# bbSMDuino_v1.net
KiCad netlist of a schematic drawn in EAGLE
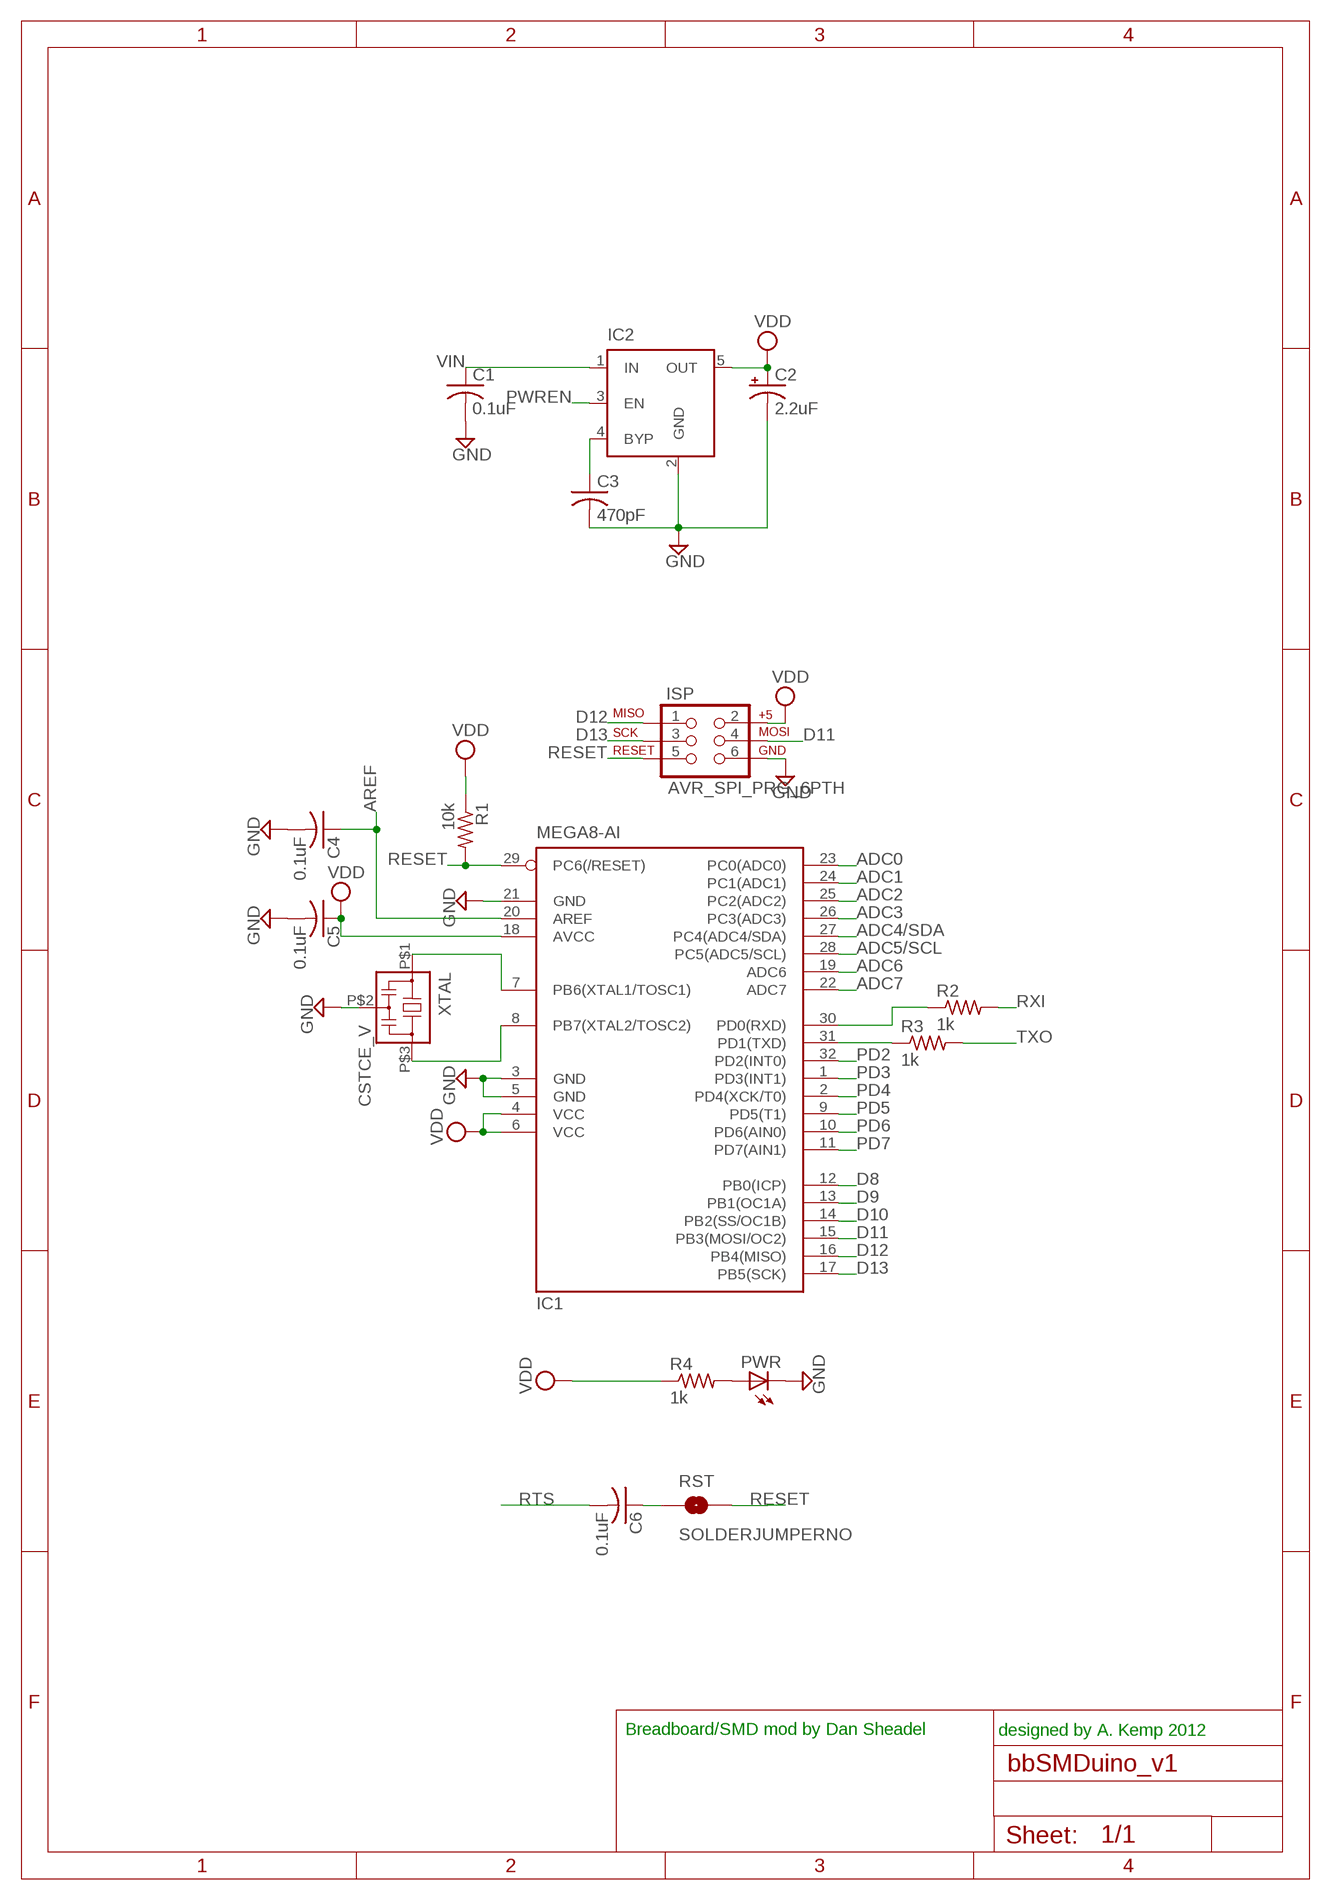
[diagram p0: schematic, sheet 1]

(export (version "E")
  (design (tool "Eeschema 10.0.6"))
  (components
    (comp (ref "C1")
      (value "0.1uF")
      (footprint "eagle-import:C0603")
      (libsource (lib "eagle-import") (part "C-USC0603"))
    )
    (comp (ref "C2")
      (value "2.2uF")
      (footprint "eagle-import:CT3216")
      (libsource (lib "eagle-import") (part "CPOL-USCT3216"))
    )
    (comp (ref "C3")
      (value "470pF")
      (footprint "eagle-import:C0603")
      (libsource (lib "eagle-import") (part "C-USC0603"))
    )
    (comp (ref "C4")
      (value "0.1uF")
      (footprint "eagle-import:C0603")
      (libsource (lib "eagle-import") (part "C-USC0603"))
    )
    (comp (ref "C5")
      (value "0.1uF")
      (footprint "eagle-import:C0603")
      (libsource (lib "eagle-import") (part "C-USC0603"))
    )
    (comp (ref "C6")
      (value "0.1uF")
      (footprint "eagle-import:C0603")
      (libsource (lib "eagle-import") (part "C-USC0603"))
    )
    (comp (ref "IC1")
      (value "MEGA8-AI")
      (footprint "eagle-import:TQFP32-08")
      (libsource (lib "eagle-import") (part "MEGA8-AI"))
    )
    (comp (ref "IC2")
      (value "MIC5219XX")
      (footprint "eagle-import:SOT23-5")
      (libsource (lib "eagle-import") (part "MIC5219XX"))
    )
    (comp (ref "ISP")
      (value "AVR_SPI_PRG_6PTH")
      (footprint "eagle-import:2X3")
      (libsource (lib "eagle-import") (part "AVR_SPI_PRG_6PTH"))
    )
    (comp (ref "PWR")
      (value "LEDCHIP-LED0603")
      (footprint "eagle-import:CHIP-LED0603")
      (libsource (lib "eagle-import") (part "LEDCHIP-LED0603"))
    )
    (comp (ref "R1")
      (value "10k")
      (footprint "eagle-import:R0603")
      (libsource (lib "eagle-import") (part "R-US_R0603"))
    )
    (comp (ref "R2")
      (value "1k")
      (footprint "eagle-import:R0603")
      (libsource (lib "eagle-import") (part "R-US_R0603"))
    )
    (comp (ref "R3")
      (value "1k")
      (footprint "eagle-import:R0603")
      (libsource (lib "eagle-import") (part "R-US_R0603"))
    )
    (comp (ref "R4")
      (value "1k")
      (footprint "eagle-import:R0603")
      (libsource (lib "eagle-import") (part "R-US_R0603"))
    )
    (comp (ref "RST")
      (value "SOLDERJUMPERNO")
      (footprint "eagle-import:SJ_2S-NO")
      (libsource (lib "eagle-import") (part "SOLDERJUMPERNO"))
    )
    (comp (ref "XTAL")
      (value "CSTCE_V")
      (footprint "eagle-import:CSTCE_V")
      (libsource (lib "eagle-import") (part "CSTCE_V"))
    )
  )
  (nets
    (net (code "1") (name "/ADC0") (class "Default")
      (node (ref "IC1") (pin "23") (pinfunction "PC0(ADC0)_23") (pintype "bidirectional"))
    )
    (net (code "2") (name "/ADC1") (class "Default")
      (node (ref "IC1") (pin "24") (pinfunction "PC1(ADC1)_24") (pintype "bidirectional"))
    )
    (net (code "3") (name "/ADC2") (class "Default")
      (node (ref "IC1") (pin "25") (pinfunction "PC2(ADC2)_25") (pintype "bidirectional"))
    )
    (net (code "4") (name "/ADC3") (class "Default")
      (node (ref "IC1") (pin "26") (pinfunction "PC3(ADC3)_26") (pintype "bidirectional"))
    )
    (net (code "5") (name "/ADC4{slash}SDA") (class "Default")
      (node (ref "IC1") (pin "27") (pinfunction "PC4(ADC4/SDA)_27") (pintype "bidirectional"))
    )
    (net (code "6") (name "/ADC5{slash}SCL") (class "Default")
      (node (ref "IC1") (pin "28") (pinfunction "PC5(ADC5/SCL)_28") (pintype "bidirectional"))
    )
    (net (code "7") (name "/ADC6") (class "Default")
      (node (ref "IC1") (pin "19") (pinfunction "ADC6_19") (pintype "bidirectional"))
    )
    (net (code "8") (name "/ADC7") (class "Default")
      (node (ref "IC1") (pin "22") (pinfunction "ADC7_22") (pintype "bidirectional"))
    )
    (net (code "9") (name "/AREF") (class "Default")
      (node (ref "C4") (pin "1") (pinfunction "1_1") (pintype "passive"))
      (node (ref "IC1") (pin "20") (pinfunction "AREF_20") (pintype "passive"))
    )
    (net (code "10") (name "/D8") (class "Default")
      (node (ref "IC1") (pin "12") (pinfunction "PB0(ICP)_12") (pintype "bidirectional"))
    )
    (net (code "11") (name "/D9") (class "Default")
      (node (ref "IC1") (pin "13") (pinfunction "PB1(OC1A)_13") (pintype "bidirectional"))
    )
    (net (code "12") (name "/D10") (class "Default")
      (node (ref "IC1") (pin "14") (pinfunction "PB2(SS/OC1B)_14") (pintype "bidirectional"))
    )
    (net (code "13") (name "/D11") (class "Default")
      (node (ref "IC1") (pin "15") (pinfunction "PB3(MOSI/OC2)_15") (pintype "bidirectional"))
      (node (ref "ISP") (pin "4") (pinfunction "4_4") (pintype "passive"))
    )
    (net (code "14") (name "/D12") (class "Default")
      (node (ref "IC1") (pin "16") (pinfunction "PB4(MISO)_16") (pintype "bidirectional"))
      (node (ref "ISP") (pin "1") (pinfunction "1_1") (pintype "passive"))
    )
    (net (code "15") (name "/D13") (class "Default")
      (node (ref "IC1") (pin "17") (pinfunction "PB5(SCK)_17") (pintype "bidirectional"))
      (node (ref "ISP") (pin "3") (pinfunction "3_3") (pintype "passive"))
    )
    (net (code "16") (name "/PD2") (class "Default")
      (node (ref "IC1") (pin "32") (pinfunction "PD2(INT0)_32") (pintype "bidirectional"))
    )
    (net (code "17") (name "/PD3") (class "Default")
      (node (ref "IC1") (pin "1") (pinfunction "PD3(INT1)_1") (pintype "bidirectional"))
    )
    (net (code "18") (name "/PD4") (class "Default")
      (node (ref "IC1") (pin "2") (pinfunction "PD4(XCK/T0)_2") (pintype "bidirectional"))
    )
    (net (code "19") (name "/PD5") (class "Default")
      (node (ref "IC1") (pin "9") (pinfunction "PD5(T1)_9") (pintype "bidirectional"))
    )
    (net (code "20") (name "/PD6") (class "Default")
      (node (ref "IC1") (pin "10") (pinfunction "PD6(AIN0)_10") (pintype "bidirectional"))
    )
    (net (code "21") (name "/PD7") (class "Default")
      (node (ref "IC1") (pin "11") (pinfunction "PD7(AIN1)_11") (pintype "bidirectional"))
    )
    (net (code "22") (name "/PWREN") (class "Default")
      (node (ref "IC2") (pin "3") (pinfunction "EN_3") (pintype "input"))
    )
    (net (code "23") (name "/RESET") (class "Default")
      (node (ref "IC1") (pin "29") (pinfunction "PC6(/RESET)_29") (pintype "bidirectional"))
      (node (ref "ISP") (pin "5") (pinfunction "5_5") (pintype "passive"))
      (node (ref "R1") (pin "2") (pinfunction "2_2") (pintype "passive"))
      (node (ref "RST") (pin "2") (pinfunction "2_2") (pintype "passive"))
    )
    (net (code "24") (name "/RTS") (class "Default")
      (node (ref "C6") (pin "2") (pinfunction "2_2") (pintype "passive"))
    )
    (net (code "25") (name "/RXI") (class "Default")
      (node (ref "R2") (pin "2") (pinfunction "2_2") (pintype "passive"))
    )
    (net (code "26") (name "/TXO") (class "Default")
      (node (ref "R3") (pin "2") (pinfunction "2_2") (pintype "passive"))
    )
    (net (code "27") (name "/VIN") (class "Default")
      (node (ref "C1") (pin "1") (pinfunction "1_1") (pintype "passive"))
      (node (ref "IC2") (pin "1") (pinfunction "IN_1") (pintype "input"))
    )
    (net (code "28") (name "GND") (class "Default")
      (node (ref "C1") (pin "2") (pinfunction "2_2") (pintype "passive"))
      (node (ref "C2") (pin "-") (pinfunction "-_-") (pintype "passive"))
      (node (ref "C3") (pin "2") (pinfunction "2_2") (pintype "passive"))
      (node (ref "C4") (pin "2") (pinfunction "2_2") (pintype "passive"))
      (node (ref "C5") (pin "2") (pinfunction "2_2") (pintype "passive"))
      (node (ref "IC1") (pin "21") (pinfunction "GND_21") (pintype "power_in"))
      (node (ref "IC1") (pin "3") (pinfunction "GND_3") (pintype "power_in"))
      (node (ref "IC1") (pin "5") (pinfunction "GND_5") (pintype "power_in"))
      (node (ref "IC2") (pin "2") (pinfunction "GND_2") (pintype "power_in"))
      (node (ref "ISP") (pin "6") (pinfunction "6_6") (pintype "passive"))
      (node (ref "PWR") (pin "C") (pinfunction "C_C") (pintype "passive"))
      (node (ref "XTAL") (pin "P$2") (pinfunction "2_P$2") (pintype "passive"))
    )
    (net (code "29") (name "Net-(C6-Pad1)") (class "Default")
      (node (ref "C6") (pin "1") (pinfunction "1_1") (pintype "passive"))
      (node (ref "RST") (pin "1") (pinfunction "1_1") (pintype "passive"))
    )
    (net (code "30") (name "Net-(IC1-PB6(XTAL1{slash}TOSC1))") (class "Default")
      (node (ref "IC1") (pin "7") (pinfunction "PB6(XTAL1/TOSC1)_7") (pintype "bidirectional"))
      (node (ref "XTAL") (pin "P$1") (pinfunction "1_P$1") (pintype "passive"))
    )
    (net (code "31") (name "Net-(IC1-PB7(XTAL2{slash}TOSC2))") (class "Default")
      (node (ref "IC1") (pin "8") (pinfunction "PB7(XTAL2/TOSC2)_8") (pintype "bidirectional"))
      (node (ref "XTAL") (pin "P$3") (pinfunction "3_P$3") (pintype "passive"))
    )
    (net (code "32") (name "Net-(IC1-PD0(RXD))") (class "Default")
      (node (ref "IC1") (pin "30") (pinfunction "PD0(RXD)_30") (pintype "bidirectional"))
      (node (ref "R2") (pin "1") (pinfunction "1_1") (pintype "passive"))
    )
    (net (code "33") (name "Net-(IC1-PD1(TXD))") (class "Default")
      (node (ref "IC1") (pin "31") (pinfunction "PD1(TXD)_31") (pintype "bidirectional"))
      (node (ref "R3") (pin "1") (pinfunction "1_1") (pintype "passive"))
    )
    (net (code "34") (name "Net-(IC2-BYP)") (class "Default")
      (node (ref "C3") (pin "1") (pinfunction "1_1") (pintype "passive"))
      (node (ref "IC2") (pin "4") (pinfunction "BYP_4") (pintype "passive"))
    )
    (net (code "35") (name "Net-(PWR-PadA)") (class "Default")
      (node (ref "PWR") (pin "A") (pinfunction "A_A") (pintype "passive"))
      (node (ref "R4") (pin "2") (pinfunction "2_2") (pintype "passive"))
    )
    (net (code "36") (name "VDD") (class "Default")
      (node (ref "C2") (pin "+") (pinfunction "+_+") (pintype "passive"))
      (node (ref "C5") (pin "1") (pinfunction "1_1") (pintype "passive"))
      (node (ref "IC1") (pin "18") (pinfunction "AVCC_18") (pintype "power_in"))
      (node (ref "IC1") (pin "4") (pinfunction "VCC_4") (pintype "power_in"))
      (node (ref "IC1") (pin "6") (pinfunction "VCC_6") (pintype "power_in"))
      (node (ref "IC2") (pin "5") (pinfunction "OUT_5") (pintype "output"))
      (node (ref "ISP") (pin "2") (pinfunction "2_2") (pintype "passive"))
      (node (ref "R1") (pin "1") (pinfunction "1_1") (pintype "passive"))
      (node (ref "R4") (pin "1") (pinfunction "1_1") (pintype "passive"))
    )
  )
)
